# SlotMachin_V1_0.net
KiCad netlist of a schematic drawn in Altium Designer
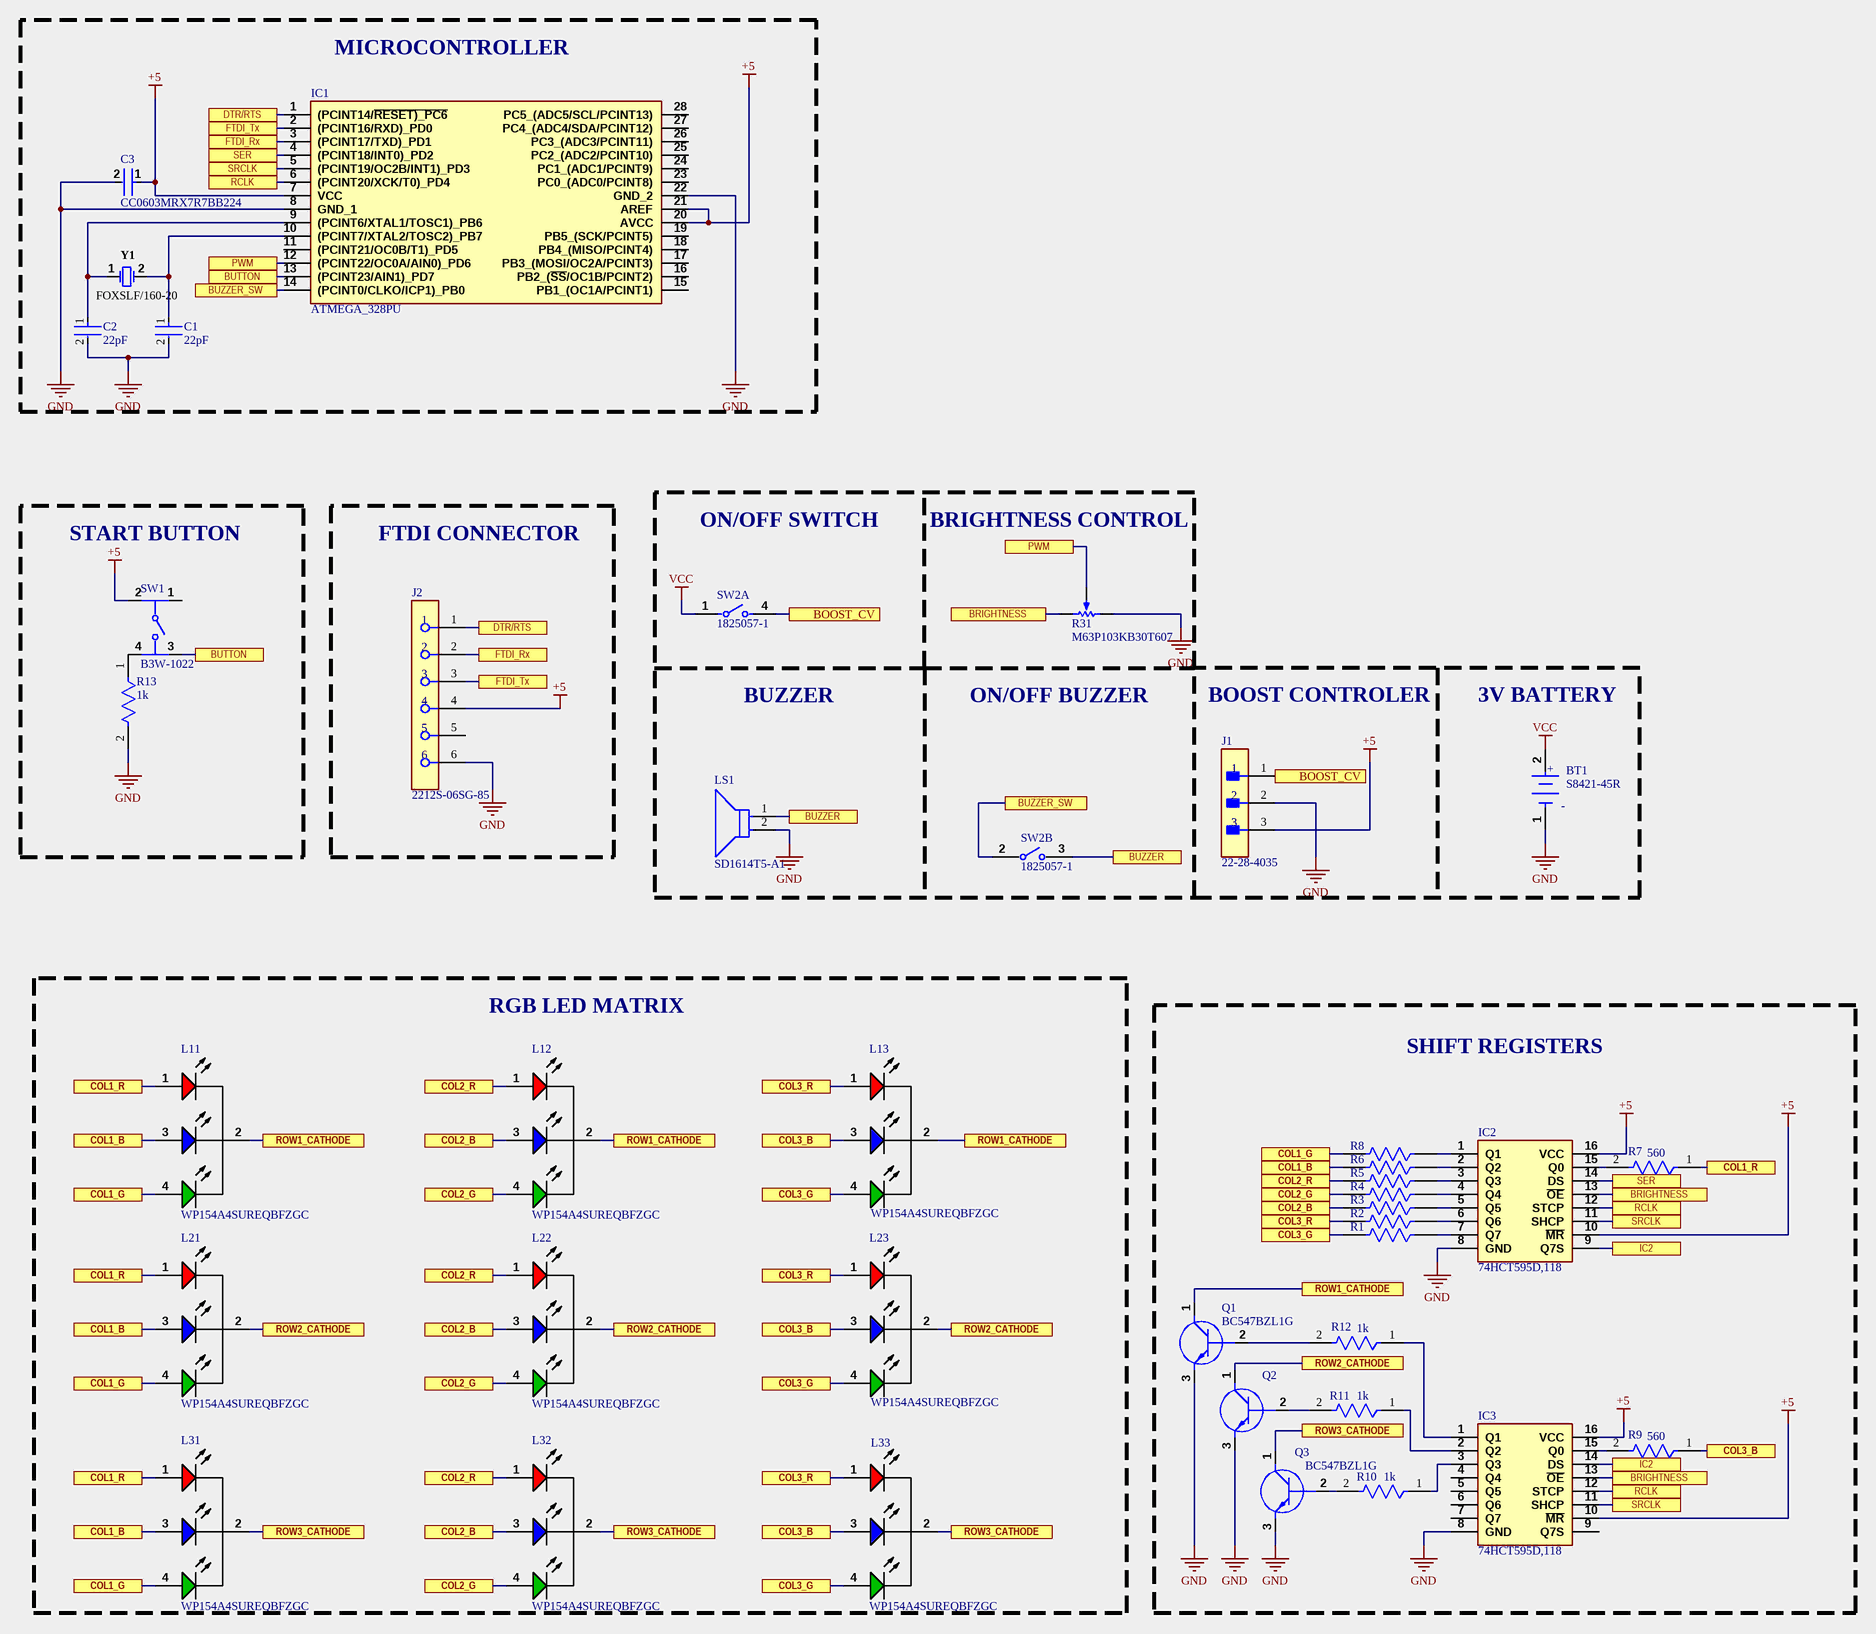
[diagram p0: SlotMachin_V1.0.SchDoc]

(export (version "E")
  (design (tool "Eeschema 10.0.6"))
  (components
    (comp (ref "BT1")
      (value "S8421-45R")
      (footprint "FP-S8421-45R-MFG")
      (description "BATTERY HOLDER COIN 20MM SMD")
      (libsource (lib "Altium Content Vault") (part "60d3b5b901a8747834971d0eb8cf3fd"))
    )
    (comp (ref "C1")
      (value "22pF")
      (footprint "FP-K221K15X7RF5TL2-MFG")
      (description "K221K15X7RF5TL2 Multilayer Ceramic Capacitor, 220 pF, 50 V, ± 10%, X7R, Radial Leaded")
      (fields (field (name "TOLERANCE") "10%"))
      (libsource (lib "Altium Content Vault") (part "b4654b650e69147ec39a6b967a45e02"))
    )
    (comp (ref "C2")
      (value "22pF")
      (footprint "FP-K221K15X7RF5TL2-MFG")
      (description "K221K15X7RF5TL2 Multilayer Ceramic Capacitor, 220 pF, 50 V, ± 10%, X7R, Radial Leaded")
      (fields (field (name "TOLERANCE") "10%"))
      (libsource (lib "Altium Content Vault") (part "b4654b650e69147ec39a6b967a45e02"))
    )
    (comp (ref "C3")
      (value "CC0603MRX7R7BB224")
      (footprint "FP-CC0603-DA-MFG")
      (description "CAP CER 0.22UF 16V X7R 0603")
      (fields (field (name "VOLTAGE") "16 V") (field (name "MANUFACTURER") "YAGEO"))
      (libsource (lib "Altium Content Vault") (part "11868f565c42a9108669ba33697ecf6"))
    )
    (comp (ref "IC1")
      (value "ATMEGA_328PU")
      (footprint "SamacSys:DIP794W56P254L3486H508Q28N")
      (description "Integrated Circuit")
      (fields (field (name "MANUFACTURER_PART_NUMBER") "ATMEGA 328PU"))
      (libsource (lib "SamacSys") (part "ATMEGA_328PU"))
    )
    (comp (ref "IC2")
      (value "74HCT595D,118")
      (footprint "SamacSys:SOIC127P600X175-16N")
      (description "Integrated Circuit")
      (fields (field (name "MOUSER PART NUMBER") "771-74HCT595D-T"))
      (libsource (lib "SamacSys") (part "74HCT595D,118"))
    )
    (comp (ref "IC3")
      (value "74HCT595D,118")
      (footprint "SamacSys:SOIC127P600X175-16N")
      (description "Integrated Circuit")
      (fields (field (name "MOUSER PART NUMBER") "771-74HCT595D-T"))
      (libsource (lib "SamacSys") (part "74HCT595D,118"))
    )
    (comp (ref "J1")
      (value "22-28-4035")
      (footprint "FP-22-28-4035-MFG")
      (libsource (lib "Altium Content Vault") (part "0d3f023dd272f625e17a2be33dea85f"))
    )
    (comp (ref "J2")
      (value "2212S-06SG-85")
      (footprint "FP-2212S-06SG-85-MFG")
      (description "Header, Rectangular, 6 Positions, Receptacle, 2.54mm pitch, Vertical, Through-Hole")
      (libsource (lib "Altium Content Vault") (part "340f86754993f25901839ab6d466df7"))
    )
    (comp (ref "L11")
      (value "WP154A4SUREQBFZGC")
      (footprint "KING-WP154A4SUREQBFZGC_V")
      (description "Full Color LED Lamp, Dominant Wavelength RGB 630 / 525 / 465 nm, -40 to 85 degC, 4-Pin THD, RoHS")
      (fields (field (name "MANUFACTURER") "Kingbright"))
      (libsource (lib "Altium Content Vault") (part "LED-RGB-AKAA-4"))
    )
    (comp (ref "L12")
      (value "WP154A4SUREQBFZGC")
      (footprint "KING-WP154A4SUREQBFZGC_V")
      (description "Full Color LED Lamp, Dominant Wavelength RGB 630 / 525 / 465 nm, -40 to 85 degC, 4-Pin THD, RoHS")
      (fields (field (name "MANUFACTURER") "Kingbright"))
      (libsource (lib "Altium Content Vault") (part "LED-RGB-AKAA-4"))
    )
    (comp (ref "L13")
      (value "WP154A4SUREQBFZGC")
      (footprint "KING-WP154A4SUREQBFZGC_V")
      (description "Full Color LED Lamp, Dominant Wavelength RGB 630 / 525 / 465 nm, -40 to 85 degC, 4-Pin THD, RoHS")
      (fields (field (name "MANUFACTURER") "Kingbright"))
      (libsource (lib "Altium Content Vault") (part "LED-RGB-AKAA-4"))
    )
    (comp (ref "L21")
      (value "WP154A4SUREQBFZGC")
      (footprint "KING-WP154A4SUREQBFZGC_V")
      (description "Full Color LED Lamp, Dominant Wavelength RGB 630 / 525 / 465 nm, -40 to 85 degC, 4-Pin THD, RoHS")
      (fields (field (name "MANUFACTURER") "Kingbright"))
      (libsource (lib "Altium Content Vault") (part "LED-RGB-AKAA-4"))
    )
    (comp (ref "L22")
      (value "WP154A4SUREQBFZGC")
      (footprint "KING-WP154A4SUREQBFZGC_V")
      (description "Full Color LED Lamp, Dominant Wavelength RGB 630 / 525 / 465 nm, -40 to 85 degC, 4-Pin THD, RoHS")
      (fields (field (name "MANUFACTURER") "Kingbright"))
      (libsource (lib "Altium Content Vault") (part "LED-RGB-AKAA-4"))
    )
    (comp (ref "L23")
      (value "WP154A4SUREQBFZGC")
      (footprint "KING-WP154A4SUREQBFZGC_V")
      (description "Full Color LED Lamp, Dominant Wavelength RGB 630 / 525 / 465 nm, -40 to 85 degC, 4-Pin THD, RoHS")
      (fields (field (name "MANUFACTURER") "Kingbright"))
      (libsource (lib "Altium Content Vault") (part "LED-RGB-AKAA-4"))
    )
    (comp (ref "L31")
      (value "WP154A4SUREQBFZGC")
      (footprint "KING-WP154A4SUREQBFZGC_V")
      (description "Full Color LED Lamp, Dominant Wavelength RGB 630 / 525 / 465 nm, -40 to 85 degC, 4-Pin THD, RoHS")
      (fields (field (name "MANUFACTURER") "Kingbright"))
      (libsource (lib "Altium Content Vault") (part "LED-RGB-AKAA-4"))
    )
    (comp (ref "L32")
      (value "WP154A4SUREQBFZGC")
      (footprint "KING-WP154A4SUREQBFZGC_V")
      (description "Full Color LED Lamp, Dominant Wavelength RGB 630 / 525 / 465 nm, -40 to 85 degC, 4-Pin THD, RoHS")
      (fields (field (name "MANUFACTURER") "Kingbright"))
      (libsource (lib "Altium Content Vault") (part "LED-RGB-AKAA-4"))
    )
    (comp (ref "L33")
      (value "WP154A4SUREQBFZGC")
      (footprint "KING-WP154A4SUREQBFZGC_V")
      (description "Full Color LED Lamp, Dominant Wavelength RGB 630 / 525 / 465 nm, -40 to 85 degC, 4-Pin THD, RoHS")
      (fields (field (name "MANUFACTURER") "Kingbright"))
      (libsource (lib "Altium Content Vault") (part "LED-RGB-AKAA-4"))
    )
    (comp (ref "LS1")
      (value "SD1614T5-A1")
      (footprint "FP-SD1614T5-A1-MFG")
      (description "BUZZER MAGNETIC 5V 80DB 2048HZ 1")
      (libsource (lib "Altium Content Vault") (part "e749a21513d54f03b70f810f265f423"))
    )
    (comp (ref "Q1")
      (value "BC547BZL1G")
      (footprint "SamacSys:BC547BZL1G")
      (description "Transistor BJT NPN")
      (fields (field (name "MOUSER PART NUMBER") "863-BC547BZL1G"))
      (libsource (lib "SamacSys") (part "BC547BZL1G"))
    )
    (comp (ref "Q2")
      (value "BC547BZL1G")
      (footprint "SamacSys:BC547BZL1G")
      (description "Transistor BJT NPN")
      (fields (field (name "MOUSER PART NUMBER") "863-BC547BZL1G"))
      (libsource (lib "SamacSys") (part "BC547BZL1G"))
    )
    (comp (ref "Q3")
      (value "BC547BZL1G")
      (footprint "SamacSys:BC547BZL1G")
      (description "Transistor BJT NPN")
      (fields (field (name "MOUSER PART NUMBER") "863-BC547BZL1G"))
      (libsource (lib "SamacSys") (part "BC547BZL1G"))
    )
    (comp (ref "R1")
      (value "560")
      (footprint "SamacSys:RESC1608X55N")
      (description "Resistor")
      (fields (field (name "MANUFACTURER_PART_NUMBER") "CPF0603B12RE"))
      (libsource (lib "SamacSys") (part "CPF0603B12RE"))
    )
    (comp (ref "R2")
      (value "560")
      (footprint "SamacSys:RESC1608X55N")
      (description "Resistor")
      (fields (field (name "MANUFACTURER_PART_NUMBER") "CPF0603B12RE"))
      (libsource (lib "SamacSys") (part "CPF0603B12RE"))
    )
    (comp (ref "R3")
      (value "560")
      (footprint "SamacSys:RESC1608X55N")
      (description "Resistor")
      (fields (field (name "MANUFACTURER_PART_NUMBER") "CPF0603B12RE"))
      (libsource (lib "SamacSys") (part "CPF0603B12RE"))
    )
    (comp (ref "R4")
      (value "560")
      (footprint "SamacSys:RESC1608X55N")
      (description "Resistor")
      (fields (field (name "MANUFACTURER_PART_NUMBER") "CPF0603B12RE"))
      (libsource (lib "SamacSys") (part "CPF0603B12RE"))
    )
    (comp (ref "R5")
      (value "560")
      (footprint "SamacSys:RESC1608X55N")
      (description "Resistor")
      (fields (field (name "MANUFACTURER_PART_NUMBER") "CPF0603B12RE"))
      (libsource (lib "SamacSys") (part "CPF0603B12RE"))
    )
    (comp (ref "R6")
      (value "560")
      (footprint "SamacSys:RESC1608X55N")
      (description "Resistor")
      (fields (field (name "MANUFACTURER_PART_NUMBER") "CPF0603B12RE"))
      (libsource (lib "SamacSys") (part "CPF0603B12RE"))
    )
    (comp (ref "R7")
      (value "560")
      (footprint "SamacSys:RESC1608X55N")
      (description "Resistor")
      (fields (field (name "MANUFACTURER_PART_NUMBER") "CPF0603B12RE"))
      (libsource (lib "") (part "CPF0603B12RE_1"))
    )
    (comp (ref "R8")
      (value "560")
      (footprint "SamacSys:RESC1608X55N")
      (description "Resistor")
      (fields (field (name "MANUFACTURER_PART_NUMBER") "CPF0603B12RE"))
      (libsource (lib "SamacSys") (part "CPF0603B12RE"))
    )
    (comp (ref "R9")
      (value "560")
      (footprint "SamacSys:RESC1608X55N")
      (description "Resistor")
      (fields (field (name "MANUFACTURER_PART_NUMBER") "CPF0603B12RE"))
      (libsource (lib "") (part "CPF0603B12RE_1"))
    )
    (comp (ref "R10")
      (value "1k")
      (footprint "SamacSys:RESC1608X55N")
      (description "Resistor")
      (fields (field (name "MANUFACTURER_PART_NUMBER") "CPF0603B12RE"))
      (libsource (lib "") (part "CPF0603B12RE_1"))
    )
    (comp (ref "R11")
      (value "1k")
      (footprint "SamacSys:RESC1608X55N")
      (description "Resistor")
      (fields (field (name "MANUFACTURER_PART_NUMBER") "CPF0603B12RE"))
      (libsource (lib "") (part "CPF0603B12RE_1"))
    )
    (comp (ref "R12")
      (value "1k")
      (footprint "SamacSys:RESC1608X55N")
      (description "Resistor")
      (fields (field (name "MANUFACTURER_PART_NUMBER") "CPF0603B12RE"))
      (libsource (lib "") (part "CPF0603B12RE_1"))
    )
    (comp (ref "R13")
      (value "1k")
      (footprint "SamacSys:RESC1608X55N")
      (description "Resistor")
      (fields (field (name "MANUFACTURER_PART_NUMBER") "CPF0603B12RE"))
      (libsource (lib "") (part "CPF0603B12RE_1"))
    )
    (comp (ref "R31")
      (value "M63P103KB30T607")
      (footprint "VISH-M63P103KB30T607")
      (description "Single-Turn Cermet Trimmer, 10 KOhm, -55 to 125 degC, 3-Pin THD, RoHS, Bulk")
      (fields (field (name "MANUFACTURER") "Vishay Semiconductor"))
      (libsource (lib "Altium Content Vault") (part "RES-POT-3"))
    )
    (comp (ref "SW1")
      (value "B3W-1022")
      (footprint "FP-B3W-1022-MFG")
      (description "SWITCH TACTILE SPST-NO 0.05A 24V")
      (libsource (lib "Altium Content Vault") (part "b8895f3f4cefb76e1819d2863dba89b"))
    )
    (comp (ref "SW2")
      (value "1825057-1")
      (footprint "FP-1825057-1-MFG")
      (description "SWITCH SLIDE DIP SPST 100MA 24V")
      (fields
        (field (name "OCTOPART") "https://octopart.com/1825057-1-te+connectivity-46507313")
        (field (name "MANUFACTURER") "TE Connectivity")
      )
      (libsource (lib "Altium Content Vault") (part "305b8df74c9585226458c49fb7f7021"))
    )
    (comp (ref "Y1")
      (value "FOXSLF/160-20")
      (footprint "FOX-FOXSLF160-20")
      (description "Resistance Weld Thru-Hole Crystal, 16 MHz, -20 to 70 degC, 2-Pin THD, RoHS, Bulk")
      (fields (field (name "TOLERANCE") "1%"))
      (libsource (lib "Altium Content Vault") (part "XTAL-1-2-2"))
    )
  )
  (nets
    (net (code "1") (name "+5") (class "Default")
      (node (ref "C3") (pin "1") (pinfunction "1_1") (pintype "passive"))
      (node (ref "IC1") (pin "20") (pinfunction "AVCC_20") (pintype "passive"))
      (node (ref "IC1") (pin "21") (pinfunction "AREF_21") (pintype "passive"))
      (node (ref "IC1") (pin "7") (pinfunction "VCC_7") (pintype "passive"))
      (node (ref "IC2") (pin "10") (pinfunction "~{MR}_10") (pintype "passive"))
      (node (ref "IC2") (pin "16") (pinfunction "VCC_16") (pintype "passive"))
      (node (ref "IC3") (pin "10") (pinfunction "~{MR}_10") (pintype "passive"))
      (node (ref "IC3") (pin "16") (pinfunction "VCC_16") (pintype "passive"))
      (node (ref "J1") (pin "3") (pinfunction "3_3") (pintype "passive"))
      (node (ref "J2") (pin "4") (pinfunction "4_4") (pintype "passive"))
      (node (ref "SW1") (pin "2") (pinfunction "2_2") (pintype "passive"))
    )
    (net (code "2") (name "/BOOST_CV") (class "Default")
      (node (ref "J1") (pin "1") (pinfunction "1_1") (pintype "passive"))
      (node (ref "SW2") (pin "4") (pinfunction "4_4") (pintype "passive"))
    )
    (net (code "3") (name "/BRIGHTNESS") (class "Default")
      (node (ref "IC2") (pin "13") (pinfunction "~{OE}_13") (pintype "passive"))
      (node (ref "IC3") (pin "13") (pinfunction "~{OE}_13") (pintype "passive"))
      (node (ref "R31") (pin "3") (pinfunction "CW_3") (pintype "passive"))
    )
    (net (code "4") (name "/BUTTON") (class "Default")
      (node (ref "IC1") (pin "13") (pinfunction "(PCINT23/AIN1)_PD7_13") (pintype "passive"))
      (node (ref "SW1") (pin "3") (pinfunction "3_3") (pintype "passive"))
    )
    (net (code "5") (name "/BUZZER") (class "Default")
      (node (ref "LS1") (pin "1") (pinfunction "C_1") (pintype "passive"))
      (node (ref "SW2") (pin "3") (pinfunction "3_3") (pintype "passive"))
    )
    (net (code "6") (name "/BUZZER_SW") (class "Default")
      (node (ref "IC1") (pin "14") (pinfunction "(PCINT0/CLKO/ICP1)_PB0_14") (pintype "passive"))
      (node (ref "SW2") (pin "2") (pinfunction "2_2") (pintype "passive"))
    )
    (net (code "7") (name "/COL1_B") (class "Default")
      (node (ref "L11") (pin "3") (pinfunction "BLUE_3") (pintype "passive"))
      (node (ref "L21") (pin "3") (pinfunction "BLUE_3") (pintype "passive"))
      (node (ref "L31") (pin "3") (pinfunction "BLUE_3") (pintype "passive"))
      (node (ref "R6") (pin "2") (pinfunction "2_2") (pintype "passive"))
    )
    (net (code "8") (name "/COL1_G") (class "Default")
      (node (ref "L11") (pin "4") (pinfunction "GREEN_4") (pintype "passive"))
      (node (ref "L21") (pin "4") (pinfunction "GREEN_4") (pintype "passive"))
      (node (ref "L31") (pin "4") (pinfunction "GREEN_4") (pintype "passive"))
      (node (ref "R8") (pin "2") (pinfunction "2_2") (pintype "passive"))
    )
    (net (code "9") (name "/COL1_R") (class "Default")
      (node (ref "L11") (pin "1") (pinfunction "RED_1") (pintype "passive"))
      (node (ref "L21") (pin "1") (pinfunction "RED_1") (pintype "passive"))
      (node (ref "L31") (pin "1") (pinfunction "RED_1") (pintype "passive"))
      (node (ref "R7") (pin "1") (pinfunction "1_1") (pintype "passive"))
    )
    (net (code "10") (name "/COL2_B") (class "Default")
      (node (ref "L12") (pin "3") (pinfunction "BLUE_3") (pintype "passive"))
      (node (ref "L22") (pin "3") (pinfunction "BLUE_3") (pintype "passive"))
      (node (ref "L32") (pin "3") (pinfunction "BLUE_3") (pintype "passive"))
      (node (ref "R3") (pin "2") (pinfunction "2_2") (pintype "passive"))
    )
    (net (code "11") (name "/COL2_G") (class "Default")
      (node (ref "L12") (pin "4") (pinfunction "GREEN_4") (pintype "passive"))
      (node (ref "L22") (pin "4") (pinfunction "GREEN_4") (pintype "passive"))
      (node (ref "L32") (pin "4") (pinfunction "GREEN_4") (pintype "passive"))
      (node (ref "R4") (pin "2") (pinfunction "2_2") (pintype "passive"))
    )
    (net (code "12") (name "/COL2_R") (class "Default")
      (node (ref "L12") (pin "1") (pinfunction "RED_1") (pintype "passive"))
      (node (ref "L22") (pin "1") (pinfunction "RED_1") (pintype "passive"))
      (node (ref "L32") (pin "1") (pinfunction "RED_1") (pintype "passive"))
      (node (ref "R5") (pin "2") (pinfunction "2_2") (pintype "passive"))
    )
    (net (code "13") (name "/COL3_B") (class "Default")
      (node (ref "L13") (pin "3") (pinfunction "BLUE_3") (pintype "passive"))
      (node (ref "L23") (pin "3") (pinfunction "BLUE_3") (pintype "passive"))
      (node (ref "L33") (pin "3") (pinfunction "BLUE_3") (pintype "passive"))
      (node (ref "R9") (pin "1") (pinfunction "1_1") (pintype "passive"))
    )
    (net (code "14") (name "/COL3_G") (class "Default")
      (node (ref "L13") (pin "4") (pinfunction "GREEN_4") (pintype "passive"))
      (node (ref "L23") (pin "4") (pinfunction "GREEN_4") (pintype "passive"))
      (node (ref "L33") (pin "4") (pinfunction "GREEN_4") (pintype "passive"))
      (node (ref "R1") (pin "2") (pinfunction "2_2") (pintype "passive"))
    )
    (net (code "15") (name "/COL3_R") (class "Default")
      (node (ref "L13") (pin "1") (pinfunction "RED_1") (pintype "passive"))
      (node (ref "L23") (pin "1") (pinfunction "RED_1") (pintype "passive"))
      (node (ref "L33") (pin "1") (pinfunction "RED_1") (pintype "passive"))
      (node (ref "R2") (pin "2") (pinfunction "2_2") (pintype "passive"))
    )
    (net (code "16") (name "/DTR{slash}RTS") (class "Default")
      (node (ref "IC1") (pin "1") (pinfunction "(PCINT14/~{RESET)_PC6}_1") (pintype "passive"))
      (node (ref "J2") (pin "1") (pinfunction "1_1") (pintype "passive"))
    )
    (net (code "17") (name "/FTDI_Rx") (class "Default")
      (node (ref "IC1") (pin "3") (pinfunction "(PCINT17/TXD)_PD1_3") (pintype "passive"))
      (node (ref "J2") (pin "2") (pinfunction "2_2") (pintype "passive"))
    )
    (net (code "18") (name "/FTDI_Tx") (class "Default")
      (node (ref "IC1") (pin "2") (pinfunction "(PCINT16/RXD)_PD0_2") (pintype "passive"))
      (node (ref "J2") (pin "3") (pinfunction "3_3") (pintype "passive"))
    )
    (net (code "19") (name "/IC2") (class "Default")
      (node (ref "IC2") (pin "9") (pinfunction "Q7S_9") (pintype "passive"))
      (node (ref "IC3") (pin "14") (pinfunction "DS_14") (pintype "passive"))
    )
    (net (code "20") (name "/PWM") (class "Default")
      (node (ref "IC1") (pin "12") (pinfunction "(PCINT22/OC0A/AIN0)_PD6_12") (pintype "passive"))
      (node (ref "R31") (pin "2") (pinfunction "S_2") (pintype "passive"))
    )
    (net (code "21") (name "/RCLK") (class "Default")
      (node (ref "IC1") (pin "6") (pinfunction "(PCINT20/XCK/T0)_PD4_6") (pintype "passive"))
      (node (ref "IC2") (pin "12") (pinfunction "STCP_12") (pintype "passive"))
      (node (ref "IC3") (pin "12") (pinfunction "STCP_12") (pintype "passive"))
    )
    (net (code "22") (name "/ROW1_CATHODE") (class "Default")
      (node (ref "L11") (pin "2") (pinfunction "CATHODE_2") (pintype "passive"))
      (node (ref "L12") (pin "2") (pinfunction "CATHODE_2") (pintype "passive"))
      (node (ref "L13") (pin "2") (pinfunction "CATHODE_2") (pintype "passive"))
      (node (ref "Q1") (pin "1") (pinfunction "C_1") (pintype "passive"))
    )
    (net (code "23") (name "/ROW2_CATHODE") (class "Default")
      (node (ref "L21") (pin "2") (pinfunction "CATHODE_2") (pintype "passive"))
      (node (ref "L22") (pin "2") (pinfunction "CATHODE_2") (pintype "passive"))
      (node (ref "L23") (pin "2") (pinfunction "CATHODE_2") (pintype "passive"))
      (node (ref "Q2") (pin "1") (pinfunction "C_1") (pintype "passive"))
    )
    (net (code "24") (name "/ROW3_CATHODE") (class "Default")
      (node (ref "L31") (pin "2") (pinfunction "CATHODE_2") (pintype "passive"))
      (node (ref "L32") (pin "2") (pinfunction "CATHODE_2") (pintype "passive"))
      (node (ref "L33") (pin "2") (pinfunction "CATHODE_2") (pintype "passive"))
      (node (ref "Q3") (pin "1") (pinfunction "C_1") (pintype "passive"))
    )
    (net (code "25") (name "/SER") (class "Default")
      (node (ref "IC1") (pin "4") (pinfunction "(PCINT18/INT0)_PD2_4") (pintype "passive"))
      (node (ref "IC2") (pin "14") (pinfunction "DS_14") (pintype "passive"))
    )
    (net (code "26") (name "/SRCLK") (class "Default")
      (node (ref "IC1") (pin "5") (pinfunction "(PCINT19/OC2B/INT1)_PD3_5") (pintype "passive"))
      (node (ref "IC2") (pin "11") (pinfunction "SHCP_11") (pintype "passive"))
      (node (ref "IC3") (pin "11") (pinfunction "SHCP_11") (pintype "passive"))
    )
    (net (code "27") (name "GND") (class "Default")
      (node (ref "BT1") (pin "1") (pinfunction "C_1") (pintype "passive"))
      (node (ref "C1") (pin "2") (pinfunction "2_2") (pintype "passive"))
      (node (ref "C2") (pin "2") (pinfunction "2_2") (pintype "passive"))
      (node (ref "C3") (pin "2") (pinfunction "2_2") (pintype "passive"))
      (node (ref "IC1") (pin "22") (pinfunction "GND_2_22") (pintype "passive"))
      (node (ref "IC1") (pin "8") (pinfunction "GND_1_8") (pintype "passive"))
      (node (ref "IC2") (pin "8") (pinfunction "GND_8") (pintype "passive"))
      (node (ref "IC3") (pin "8") (pinfunction "GND_8") (pintype "passive"))
      (node (ref "J1") (pin "2") (pinfunction "2_2") (pintype "passive"))
      (node (ref "J2") (pin "6") (pinfunction "6_6") (pintype "passive"))
      (node (ref "LS1") (pin "2") (pinfunction "A_2") (pintype "passive"))
      (node (ref "Q1") (pin "3") (pinfunction "E_3") (pintype "passive"))
      (node (ref "Q2") (pin "3") (pinfunction "E_3") (pintype "passive"))
      (node (ref "Q3") (pin "3") (pinfunction "E_3") (pintype "passive"))
      (node (ref "R13") (pin "2") (pinfunction "2_2") (pintype "passive"))
      (node (ref "R31") (pin "1") (pinfunction "CCW_1") (pintype "passive"))
    )
    (net (code "28") (name "Net-(IC1-(PCINT6{slash}XTAL1{slash}TOSC1)_PB6)") (class "Default")
      (node (ref "C2") (pin "1") (pinfunction "1_1") (pintype "passive"))
      (node (ref "IC1") (pin "9") (pinfunction "(PCINT6/XTAL1/TOSC1)_PB6_9") (pintype "passive"))
      (node (ref "Y1") (pin "1") (pinfunction "1_1") (pintype "passive"))
    )
    (net (code "29") (name "Net-(IC1-(PCINT7{slash}XTAL2{slash}TOSC2)_PB7)") (class "Default")
      (node (ref "C1") (pin "1") (pinfunction "1_1") (pintype "passive"))
      (node (ref "IC1") (pin "10") (pinfunction "(PCINT7/XTAL2/TOSC2)_PB7_10") (pintype "passive"))
      (node (ref "Y1") (pin "2") (pinfunction "2_2") (pintype "passive"))
    )
    (net (code "30") (name "Net-(IC2-Q0)") (class "Default")
      (node (ref "IC2") (pin "15") (pinfunction "Q0_15") (pintype "passive"))
      (node (ref "R7") (pin "2") (pinfunction "2_2") (pintype "passive"))
    )
    (net (code "31") (name "Net-(IC2-Q1)") (class "Default")
      (node (ref "IC2") (pin "1") (pinfunction "Q1_1") (pintype "passive"))
      (node (ref "R8") (pin "1") (pinfunction "1_1") (pintype "passive"))
    )
    (net (code "32") (name "Net-(IC2-Q2)") (class "Default")
      (node (ref "IC2") (pin "2") (pinfunction "Q2_2") (pintype "passive"))
      (node (ref "R6") (pin "1") (pinfunction "1_1") (pintype "passive"))
    )
    (net (code "33") (name "Net-(IC2-Q3)") (class "Default")
      (node (ref "IC2") (pin "3") (pinfunction "Q3_3") (pintype "passive"))
      (node (ref "R5") (pin "1") (pinfunction "1_1") (pintype "passive"))
    )
    (net (code "34") (name "Net-(IC2-Q4)") (class "Default")
      (node (ref "IC2") (pin "4") (pinfunction "Q4_4") (pintype "passive"))
      (node (ref "R4") (pin "1") (pinfunction "1_1") (pintype "passive"))
    )
    (net (code "35") (name "Net-(IC2-Q5)") (class "Default")
      (node (ref "IC2") (pin "5") (pinfunction "Q5_5") (pintype "passive"))
      (node (ref "R3") (pin "1") (pinfunction "1_1") (pintype "passive"))
    )
    (net (code "36") (name "Net-(IC2-Q6)") (class "Default")
      (node (ref "IC2") (pin "6") (pinfunction "Q6_6") (pintype "passive"))
      (node (ref "R2") (pin "1") (pinfunction "1_1") (pintype "passive"))
    )
    (net (code "37") (name "Net-(IC2-Q7)") (class "Default")
      (node (ref "IC2") (pin "7") (pinfunction "Q7_7") (pintype "passive"))
      (node (ref "R1") (pin "1") (pinfunction "1_1") (pintype "passive"))
    )
    (net (code "38") (name "Net-(IC3-Q0)") (class "Default")
      (node (ref "IC3") (pin "15") (pinfunction "Q0_15") (pintype "passive"))
      (node (ref "R9") (pin "2") (pinfunction "2_2") (pintype "passive"))
    )
    (net (code "39") (name "Net-(IC3-Q1)") (class "Default")
      (node (ref "IC3") (pin "1") (pinfunction "Q1_1") (pintype "passive"))
      (node (ref "R12") (pin "1") (pinfunction "1_1") (pintype "passive"))
    )
    (net (code "40") (name "Net-(IC3-Q2)") (class "Default")
      (node (ref "IC3") (pin "2") (pinfunction "Q2_2") (pintype "passive"))
      (node (ref "R11") (pin "1") (pinfunction "1_1") (pintype "passive"))
    )
    (net (code "41") (name "Net-(IC3-Q3)") (class "Default")
      (node (ref "IC3") (pin "3") (pinfunction "Q3_3") (pintype "passive"))
      (node (ref "R10") (pin "1") (pinfunction "1_1") (pintype "passive"))
    )
    (net (code "42") (name "Net-(Q1-B)") (class "Default")
      (node (ref "Q1") (pin "2") (pinfunction "B_2") (pintype "passive"))
      (node (ref "R12") (pin "2") (pinfunction "2_2") (pintype "passive"))
    )
    (net (code "43") (name "Net-(Q2-B)") (class "Default")
      (node (ref "Q2") (pin "2") (pinfunction "B_2") (pintype "passive"))
      (node (ref "R11") (pin "2") (pinfunction "2_2") (pintype "passive"))
    )
    (net (code "44") (name "Net-(Q3-B)") (class "Default")
      (node (ref "Q3") (pin "2") (pinfunction "B_2") (pintype "passive"))
      (node (ref "R10") (pin "2") (pinfunction "2_2") (pintype "passive"))
    )
    (net (code "45") (name "Net-(R13-Pad1)") (class "Default")
      (node (ref "R13") (pin "1") (pinfunction "1_1") (pintype "passive"))
      (node (ref "SW1") (pin "4") (pinfunction "4_4") (pintype "passive"))
    )
    (net (code "46") (name "VCC") (class "Default")
      (node (ref "BT1") (pin "2") (pinfunction "A_2") (pintype "passive"))
      (node (ref "SW2") (pin "1") (pinfunction "1_1") (pintype "passive"))
    )
    (net (code "47") (name "unconnected-(IC1-(PCINT21{slash}OC0B{slash}T1)_PD5-Pad11)") (class "Default")
      (node (ref "IC1") (pin "11") (pinfunction "(PCINT21/OC0B/T1)_PD5_11") (pintype "passive"))
    )
    (net (code "48") (name "unconnected-(IC1-PB1_(OC1A{slash}PCINT1)-Pad15)") (class "Default")
      (node (ref "IC1") (pin "15") (pinfunction "PB1_(OC1A/PCINT1)_15") (pintype "passive"))
    )
    (net (code "49") (name "unconnected-(IC1-PB2_(~{SS}{slash}OC1B{slash}PCINT2)-Pad16)") (class "Default")
      (node (ref "IC1") (pin "16") (pinfunction "PB2_(~{SS}/OC1B/PCINT2)_16") (pintype "passive"))
    )
    (net (code "50") (name "unconnected-(IC1-PB3_(MOSI{slash}OC2A{slash}PCINT3)-Pad17)") (class "Default")
      (node (ref "IC1") (pin "17") (pinfunction "PB3_(MOSI/OC2A/PCINT3)_17") (pintype "passive"))
    )
    (net (code "51") (name "unconnected-(IC1-PB4_(MISO{slash}PCINT4)-Pad18)") (class "Default")
      (node (ref "IC1") (pin "18") (pinfunction "PB4_(MISO/PCINT4)_18") (pintype "passive"))
    )
    (net (code "52") (name "unconnected-(IC1-PB5_(SCK{slash}PCINT5)-Pad19)") (class "Default")
      (node (ref "IC1") (pin "19") (pinfunction "PB5_(SCK/PCINT5)_19") (pintype "passive"))
    )
    (net (code "53") (name "unconnected-(IC1-PC0_(ADC0{slash}PCINT8)-Pad23)") (class "Default")
      (node (ref "IC1") (pin "23") (pinfunction "PC0_(ADC0/PCINT8)_23") (pintype "passive"))
    )
    (net (code "54") (name "unconnected-(IC1-PC1_(ADC1{slash}PCINT9)-Pad24)") (class "Default")
      (node (ref "IC1") (pin "24") (pinfunction "PC1_(ADC1/PCINT9)_24") (pintype "passive"))
    )
    (net (code "55") (name "unconnected-(IC1-PC2_(ADC2{slash}PCINT10)-Pad25)") (class "Default")
      (node (ref "IC1") (pin "25") (pinfunction "PC2_(ADC2/PCINT10)_25") (pintype "passive"))
    )
    (net (code "56") (name "unconnected-(IC1-PC3_(ADC3{slash}PCINT11)-Pad26)") (class "Default")
      (node (ref "IC1") (pin "26") (pinfunction "PC3_(ADC3/PCINT11)_26") (pintype "passive"))
    )
    (net (code "57") (name "unconnected-(IC1-PC4_(ADC4{slash}SDA{slash}PCINT12)-Pad27)") (class "Default")
      (node (ref "IC1") (pin "27") (pinfunction "PC4_(ADC4/SDA/PCINT12)_27") (pintype "passive"))
    )
    (net (code "58") (name "unconnected-(IC1-PC5_(ADC5{slash}SCL{slash}PCINT13)-Pad28)") (class "Default")
      (node (ref "IC1") (pin "28") (pinfunction "PC5_(ADC5/SCL/PCINT13)_28") (pintype "passive"))
    )
    (net (code "59") (name "unconnected-(IC3-Q4-Pad4)") (class "Default")
      (node (ref "IC3") (pin "4") (pinfunction "Q4_4") (pintype "passive"))
    )
    (net (code "60") (name "unconnected-(IC3-Q5-Pad5)") (class "Default")
      (node (ref "IC3") (pin "5") (pinfunction "Q5_5") (pintype "passive"))
    )
    (net (code "61") (name "unconnected-(IC3-Q6-Pad6)") (class "Default")
      (node (ref "IC3") (pin "6") (pinfunction "Q6_6") (pintype "passive"))
    )
    (net (code "62") (name "unconnected-(IC3-Q7-Pad7)") (class "Default")
      (node (ref "IC3") (pin "7") (pinfunction "Q7_7") (pintype "passive"))
    )
    (net (code "63") (name "unconnected-(IC3-Q7S-Pad9)") (class "Default")
      (node (ref "IC3") (pin "9") (pinfunction "Q7S_9") (pintype "passive"))
    )
    (net (code "64") (name "unconnected-(J2-Pad5)") (class "Default")
      (node (ref "J2") (pin "5") (pinfunction "5_5") (pintype "passive"))
    )
    (net (code "65") (name "unconnected-(SW1-Pad1)") (class "Default")
      (node (ref "SW1") (pin "1") (pinfunction "1_1") (pintype "passive"))
    )
  )
)
